# airrelay.net
KiCad netlist of a schematic drawn in EAGLE
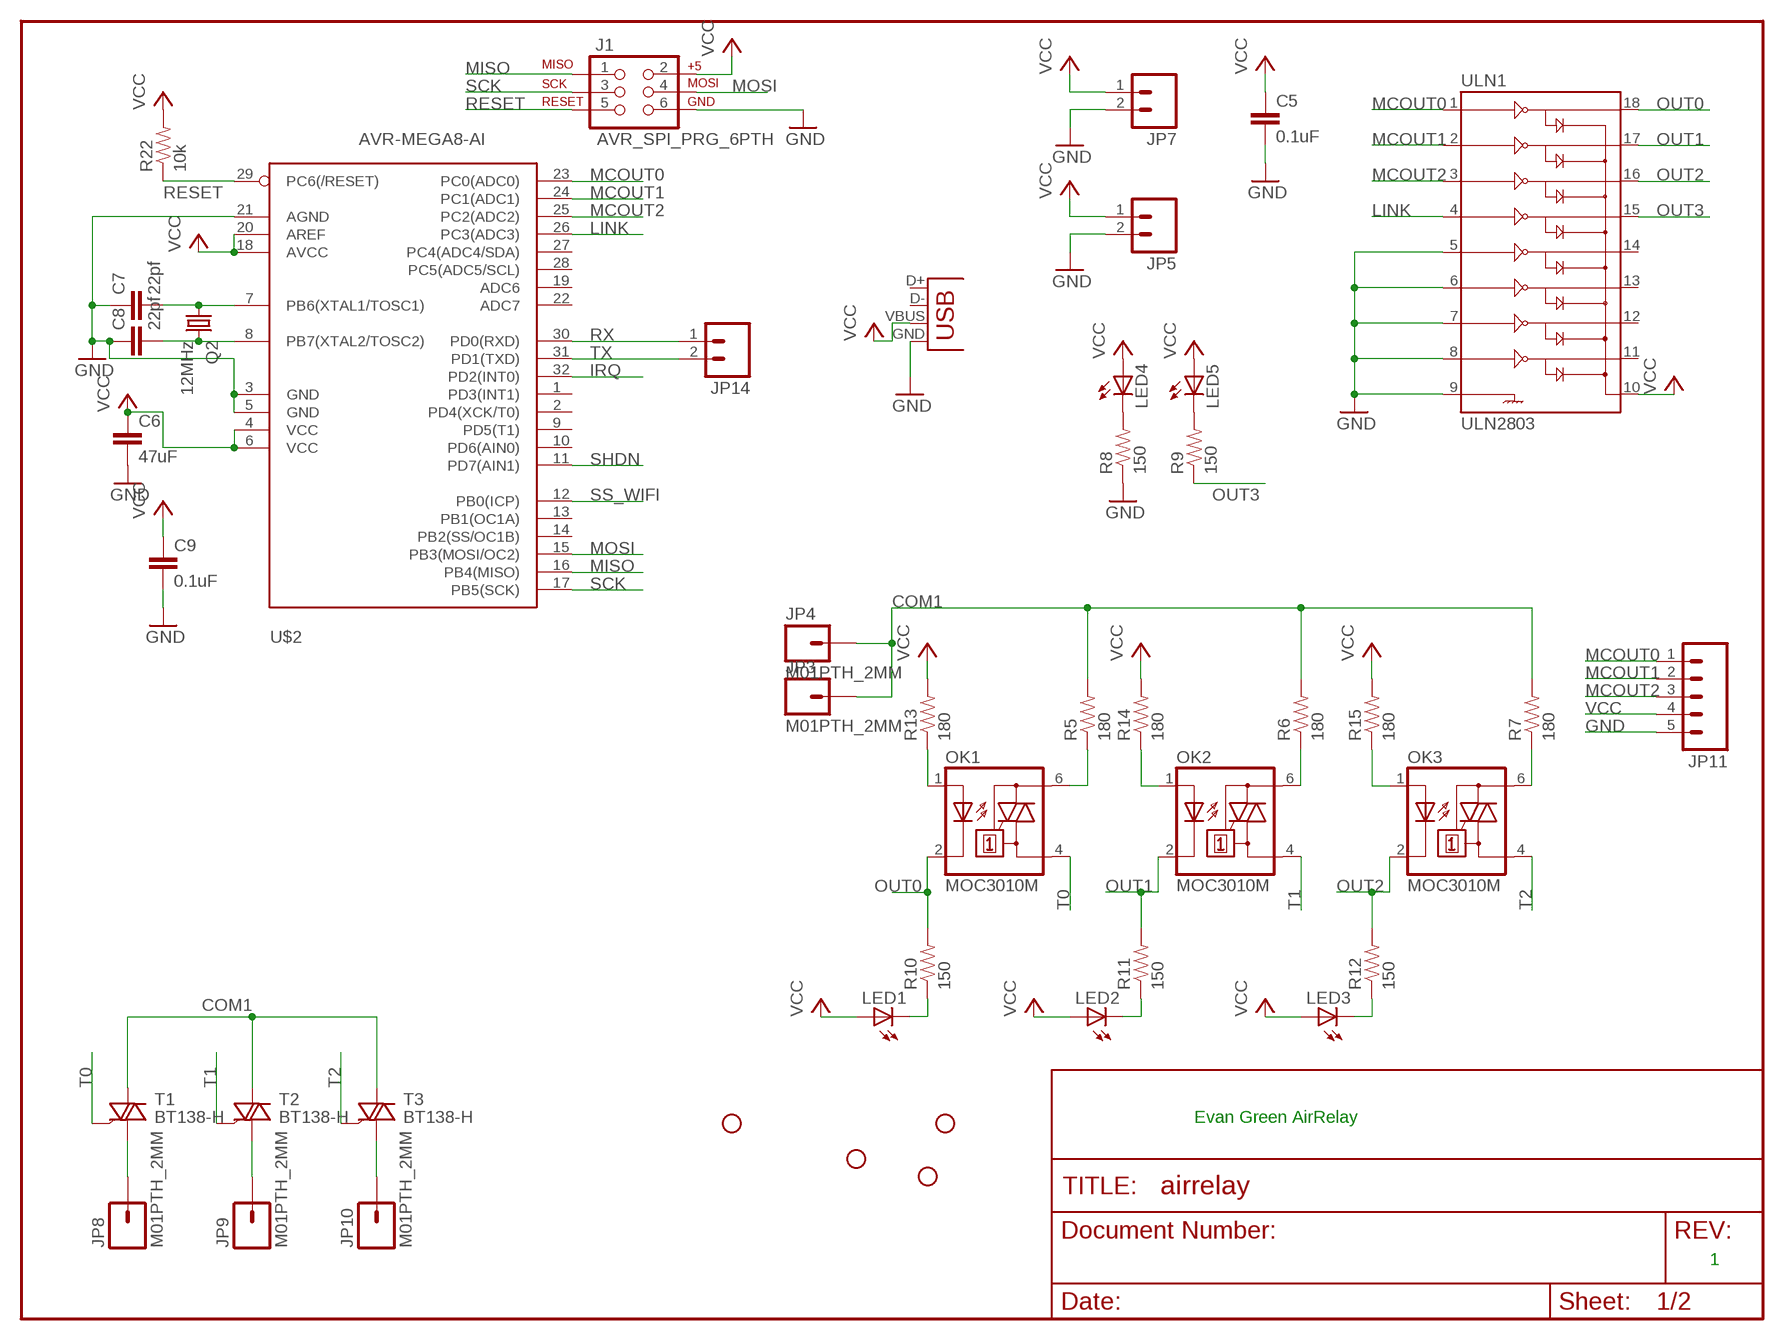
[diagram p0: schematic, sheet 1]
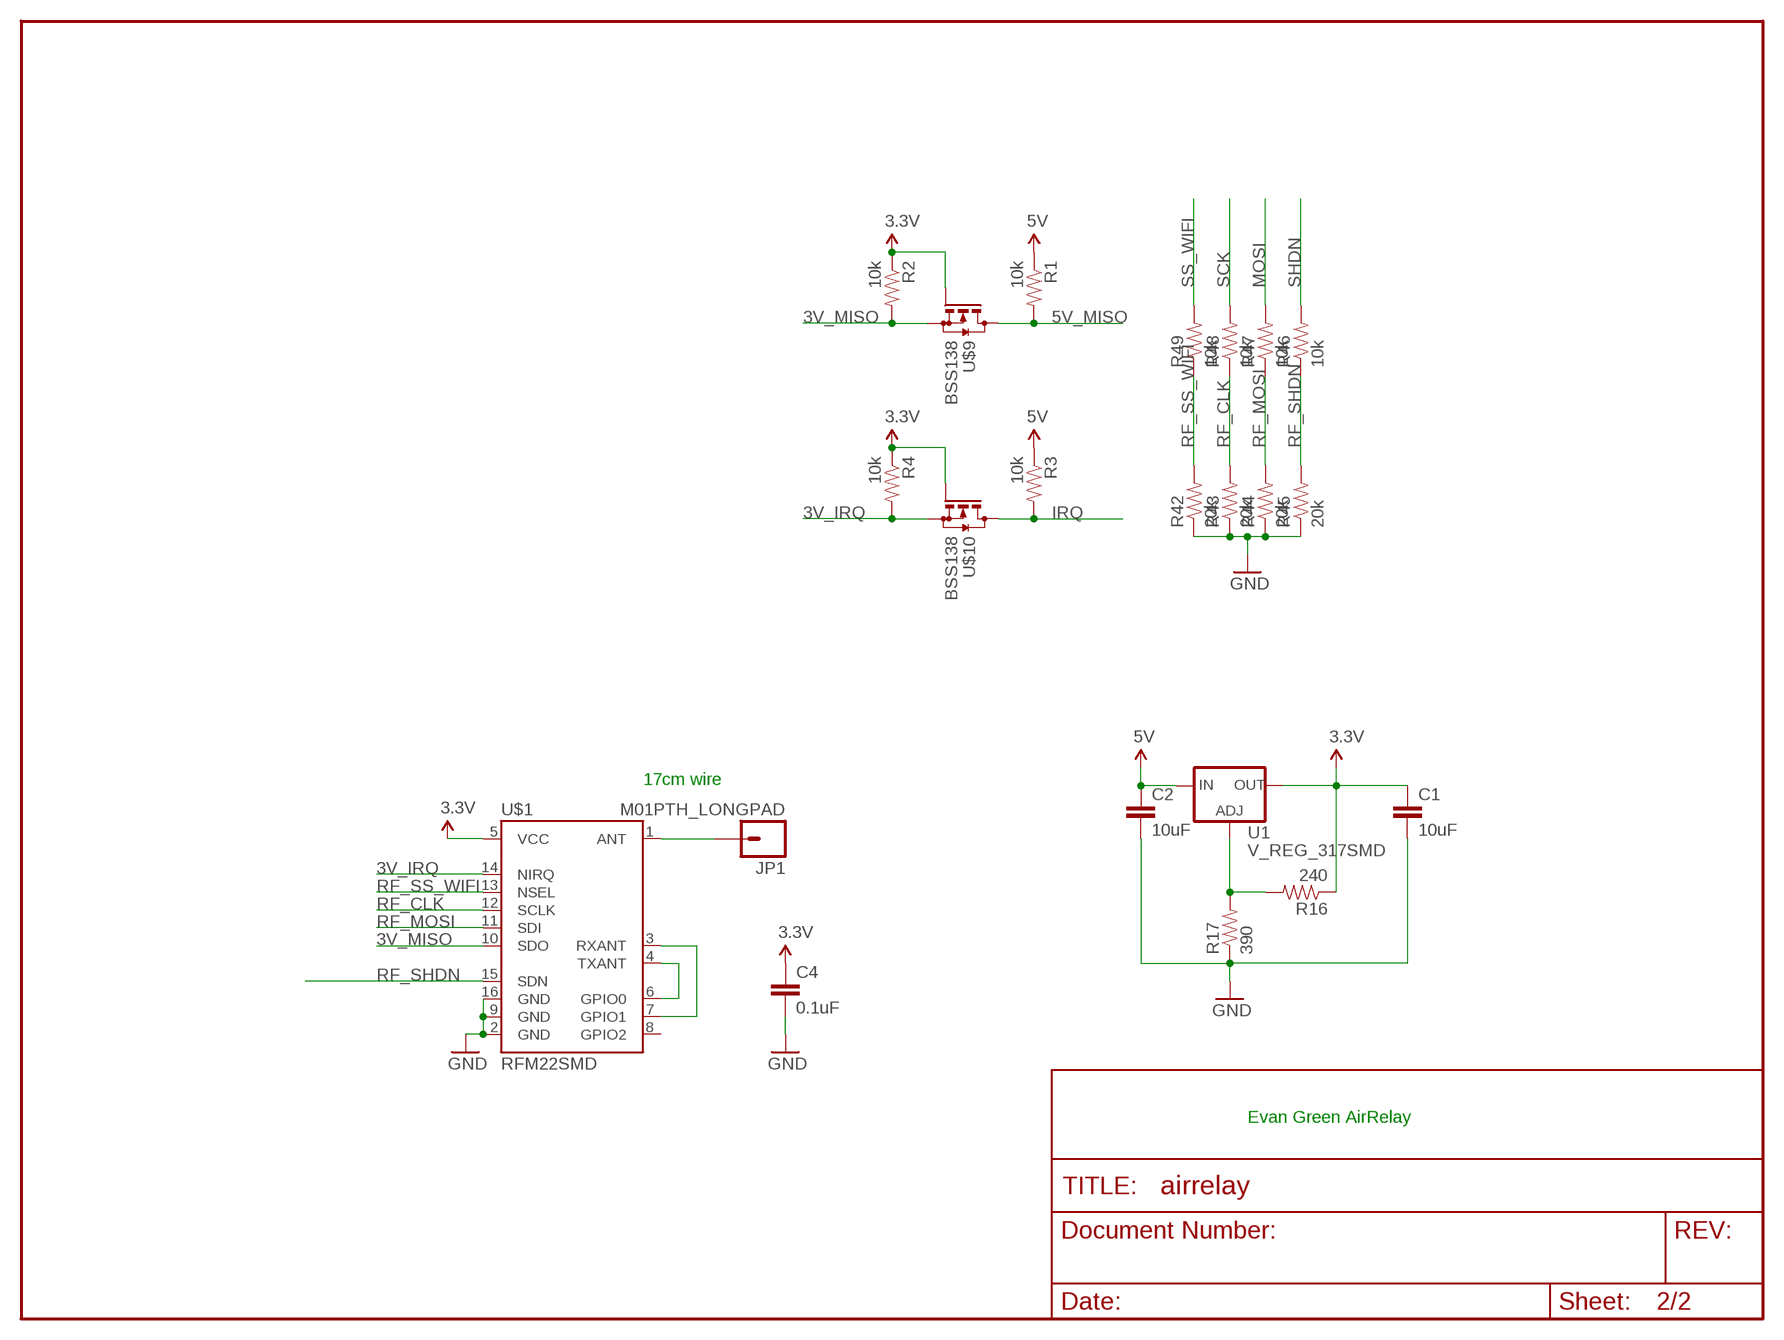
[diagram p1: schematic, sheet 2]

(export (version "E")
  (design (tool "Eeschema 10.0.6"))
  (components
    (comp (ref "C5")
      (value "0.1uF")
      (footprint "eagle-import:0402-CAP")
      (libsource (lib "eagle-import") (part "CAP0402-CAP"))
    )
    (comp (ref "C6")
      (value "47uF")
      (footprint "eagle-import:1210")
      (libsource (lib "eagle-import") (part "CAP1210"))
    )
    (comp (ref "C7")
      (value "22pf")
      (footprint "eagle-import:0402-CAP")
      (libsource (lib "eagle-import") (part "CAP0402-CAP"))
    )
    (comp (ref "C8")
      (value "22pf")
      (footprint "eagle-import:0402-CAP")
      (libsource (lib "eagle-import") (part "CAP0402-CAP"))
    )
    (comp (ref "C9")
      (value "0.1uF")
      (footprint "eagle-import:0402-CAP")
      (libsource (lib "eagle-import") (part "CAP0402-CAP"))
    )
    (comp (ref "J1")
      (value "AVR_SPI_PRG_6PTH")
      (footprint "eagle-import:2X3")
      (libsource (lib "eagle-import") (part "AVR_SPI_PRG_6PTH"))
    )
    (comp (ref "JP2")
      (value "STAND-OFF")
      (footprint "eagle-import:STAND-OFF")
      (libsource (lib "eagle-import") (part "STAND-OFF"))
    )
    (comp (ref "JP3")
      (value "M01PTH_2MM")
      (footprint "eagle-import:1X01_2MM")
      (libsource (lib "eagle-import") (part "M01PTH_2MM"))
    )
    (comp (ref "JP4")
      (value "M01PTH_2MM")
      (footprint "eagle-import:1X01_2MM")
      (libsource (lib "eagle-import") (part "M01PTH_2MM"))
    )
    (comp (ref "JP5")
      (value "M02PTH")
      (footprint "eagle-import:1X02")
      (libsource (lib "eagle-import") (part "M02PTH"))
    )
    (comp (ref "JP6")
      (value "STAND-OFF")
      (footprint "eagle-import:STAND-OFF")
      (libsource (lib "eagle-import") (part "STAND-OFF"))
    )
    (comp (ref "JP7")
      (value "M02PTH")
      (footprint "eagle-import:1X02")
      (libsource (lib "eagle-import") (part "M02PTH"))
    )
    (comp (ref "JP8")
      (value "M01PTH_2MM")
      (footprint "eagle-import:1X01_2MM")
      (libsource (lib "eagle-import") (part "M01PTH_2MM"))
    )
    (comp (ref "JP9")
      (value "M01PTH_2MM")
      (footprint "eagle-import:1X01_2MM")
      (libsource (lib "eagle-import") (part "M01PTH_2MM"))
    )
    (comp (ref "JP10")
      (value "M01PTH_2MM")
      (footprint "eagle-import:1X01_2MM")
      (libsource (lib "eagle-import") (part "M01PTH_2MM"))
    )
    (comp (ref "JP11")
      (value "M05PTH")
      (footprint "eagle-import:1X05")
      (libsource (lib "eagle-import") (part "M05PTH"))
    )
    (comp (ref "JP12")
      (value "STAND-OFF")
      (footprint "eagle-import:STAND-OFF")
      (libsource (lib "eagle-import") (part "STAND-OFF"))
    )
    (comp (ref "JP13")
      (value "STAND-OFF")
      (footprint "eagle-import:STAND-OFF")
      (libsource (lib "eagle-import") (part "STAND-OFF"))
    )
    (comp (ref "JP14")
      (value "M02PTH")
      (footprint "eagle-import:1X02")
      (libsource (lib "eagle-import") (part "M02PTH"))
    )
    (comp (ref "LED1")
      (value "LED5MM")
      (footprint "eagle-import:LED5MM")
      (libsource (lib "eagle-import") (part "LED5MM"))
    )
    (comp (ref "LED2")
      (value "LED5MM")
      (footprint "eagle-import:LED5MM")
      (libsource (lib "eagle-import") (part "LED5MM"))
    )
    (comp (ref "LED3")
      (value "LED5MM")
      (footprint "eagle-import:LED5MM")
      (libsource (lib "eagle-import") (part "LED5MM"))
    )
    (comp (ref "LED4")
      (value "LED3MM")
      (footprint "eagle-import:LED3MM")
      (libsource (lib "eagle-import") (part "LED3MM"))
    )
    (comp (ref "LED5")
      (value "LED3MM")
      (footprint "eagle-import:LED3MM")
      (libsource (lib "eagle-import") (part "LED3MM"))
    )
    (comp (ref "OK1")
      (value "MOC3010M")
      (footprint "eagle-import:DIL06")
      (fields (field (name "MF") "FAIRCHILD SEMICONDUCTOR") (field (name "MPN") "MOC3010-M"))
      (libsource (lib "eagle-import") (part "MOC30M10"))
    )
    (comp (ref "OK2")
      (value "MOC3010M")
      (footprint "eagle-import:DIL06")
      (fields (field (name "MF") "FAIRCHILD SEMICONDUCTOR") (field (name "MPN") "MOC3010-M"))
      (libsource (lib "eagle-import") (part "MOC30M10"))
    )
    (comp (ref "OK3")
      (value "MOC3010M")
      (footprint "eagle-import:DIL06")
      (fields (field (name "MF") "FAIRCHILD SEMICONDUCTOR") (field (name "MPN") "MOC3010-M"))
      (libsource (lib "eagle-import") (part "MOC30M10"))
    )
    (comp (ref "Q2")
      (value "12MHz")
      (footprint "eagle-import:TC38H")
      (libsource (lib "eagle-import") (part "CRYSTALTC38H"))
    )
    (comp (ref "R5")
      (value "180")
      (footprint "eagle-import:AXIAL-0.4")
      (libsource (lib "eagle-import") (part "RESISTORPTH-1/4W"))
    )
    (comp (ref "R6")
      (value "180")
      (footprint "eagle-import:AXIAL-0.4")
      (libsource (lib "eagle-import") (part "RESISTORPTH-1/4W"))
    )
    (comp (ref "R7")
      (value "180")
      (footprint "eagle-import:AXIAL-0.4")
      (libsource (lib "eagle-import") (part "RESISTORPTH-1/4W"))
    )
    (comp (ref "R8")
      (value "150")
      (footprint "eagle-import:0402-RES")
      (libsource (lib "eagle-import") (part "RESISTOR0402-RES"))
    )
    (comp (ref "R9")
      (value "150")
      (footprint "eagle-import:0402-RES")
      (libsource (lib "eagle-import") (part "RESISTOR0402-RES"))
    )
    (comp (ref "R10")
      (value "150")
      (footprint "eagle-import:0402-RES")
      (libsource (lib "eagle-import") (part "RESISTOR0402-RES"))
    )
    (comp (ref "R11")
      (value "150")
      (footprint "eagle-import:0402-RES")
      (libsource (lib "eagle-import") (part "RESISTOR0402-RES"))
    )
    (comp (ref "R12")
      (value "150")
      (footprint "eagle-import:0402-RES")
      (libsource (lib "eagle-import") (part "RESISTOR0402-RES"))
    )
    (comp (ref "R13")
      (value "180")
      (footprint "eagle-import:0402-RES")
      (libsource (lib "eagle-import") (part "RESISTOR0402-RES"))
    )
    (comp (ref "R14")
      (value "180")
      (footprint "eagle-import:0402-RES")
      (libsource (lib "eagle-import") (part "RESISTOR0402-RES"))
    )
    (comp (ref "R15")
      (value "180")
      (footprint "eagle-import:0402-RES")
      (libsource (lib "eagle-import") (part "RESISTOR0402-RES"))
    )
    (comp (ref "R22")
      (value "10k")
      (footprint "eagle-import:0402-RES")
      (libsource (lib "eagle-import") (part "RESISTOR0402-RES"))
    )
    (comp (ref "T1")
      (value "BT138-H")
      (footprint "eagle-import:TO220BH")
      (libsource (lib "eagle-import") (part "BT138-H"))
    )
    (comp (ref "T2")
      (value "BT138-H")
      (footprint "eagle-import:TO220BH")
      (libsource (lib "eagle-import") (part "BT138-H"))
    )
    (comp (ref "T3")
      (value "BT138-H")
      (footprint "eagle-import:TO220BH")
      (libsource (lib "eagle-import") (part "BT138-H"))
    )
    (comp (ref "U$2")
      (value "AVR-MEGA8-AI")
      (footprint "eagle-import:TQFP32-08")
      (libsource (lib "eagle-import") (part "AVR-MEGA8-AI"))
    )
    (comp (ref "ULN1")
      (value "ULN2803")
      (footprint "eagle-import:SO18L")
      (libsource (lib "eagle-import") (part "ULN2803SOICW"))
    )
    (comp (ref "X1")
      (value "USBSMD")
      (footprint "eagle-import:USB-MINIB")
      (libsource (lib "eagle-import") (part "USBSMD"))
    )
    (comp (ref "C1")
      (value "10uF")
      (footprint "eagle-import:0805")
      (libsource (lib "eagle-import") (part "CAP0805"))
    )
    (comp (ref "C2")
      (value "10uF")
      (footprint "eagle-import:0805")
      (libsource (lib "eagle-import") (part "CAP0805"))
    )
    (comp (ref "C4")
      (value "0.1uF")
      (footprint "eagle-import:0402-CAP")
      (libsource (lib "eagle-import") (part "CAP0402-CAP"))
    )
    (comp (ref "JP1")
      (value "M01PTH_LONGPAD")
      (footprint "eagle-import:1X01_LONGPAD")
      (libsource (lib "eagle-import") (part "M01PTH_LONGPAD"))
    )
    (comp (ref "R1")
      (value "10k")
      (footprint "eagle-import:0402-RES")
      (libsource (lib "eagle-import") (part "RESISTOR0402-RES"))
    )
    (comp (ref "R2")
      (value "10k")
      (footprint "eagle-import:0402-RES")
      (libsource (lib "eagle-import") (part "RESISTOR0402-RES"))
    )
    (comp (ref "R3")
      (value "10k")
      (footprint "eagle-import:0402-RES")
      (libsource (lib "eagle-import") (part "RESISTOR0402-RES"))
    )
    (comp (ref "R4")
      (value "10k")
      (footprint "eagle-import:0402-RES")
      (libsource (lib "eagle-import") (part "RESISTOR0402-RES"))
    )
    (comp (ref "R16")
      (value "240")
      (footprint "eagle-import:0402-RES")
      (libsource (lib "eagle-import") (part "RESISTOR0402-RES"))
    )
    (comp (ref "R17")
      (value "390")
      (footprint "eagle-import:0402-RES")
      (libsource (lib "eagle-import") (part "RESISTOR0402-RES"))
    )
    (comp (ref "R42")
      (value "20k")
      (footprint "eagle-import:0402-RES")
      (libsource (lib "eagle-import") (part "RESISTOR0402-RES"))
    )
    (comp (ref "R43")
      (value "20k")
      (footprint "eagle-import:0402-RES")
      (libsource (lib "eagle-import") (part "RESISTOR0402-RES"))
    )
    (comp (ref "R44")
      (value "20k")
      (footprint "eagle-import:0402-RES")
      (libsource (lib "eagle-import") (part "RESISTOR0402-RES"))
    )
    (comp (ref "R45")
      (value "20k")
      (footprint "eagle-import:0402-RES")
      (libsource (lib "eagle-import") (part "RESISTOR0402-RES"))
    )
    (comp (ref "R46")
      (value "10k")
      (footprint "eagle-import:0402-RES")
      (libsource (lib "eagle-import") (part "RESISTOR0402-RES"))
    )
    (comp (ref "R47")
      (value "10k")
      (footprint "eagle-import:0402-RES")
      (libsource (lib "eagle-import") (part "RESISTOR0402-RES"))
    )
    (comp (ref "R48")
      (value "10k")
      (footprint "eagle-import:0402-RES")
      (libsource (lib "eagle-import") (part "RESISTOR0402-RES"))
    )
    (comp (ref "R49")
      (value "10k")
      (footprint "eagle-import:0402-RES")
      (libsource (lib "eagle-import") (part "RESISTOR0402-RES"))
    )
    (comp (ref "U$1")
      (value "RFM22SMD")
      (footprint "eagle-import:RFM22-XXX-S2")
      (libsource (lib "eagle-import") (part "RFM22SMD"))
    )
    (comp (ref "U$9")
      (value "BSS138")
      (footprint "eagle-import:SOT-323")
      (libsource (lib "eagle-import") (part "BSS138"))
    )
    (comp (ref "U$10")
      (value "BSS138")
      (footprint "eagle-import:SOT-323")
      (libsource (lib "eagle-import") (part "BSS138"))
    )
    (comp (ref "U1")
      (value "V_REG_317SMD")
      (footprint "eagle-import:SOT223")
      (libsource (lib "eagle-import") (part "V_REG_317SMD"))
    )
  )
  (nets
    (net (code "1") (name "3.3V") (class "Default")
      (node (ref "C1") (pin "1") (pinfunction "1_1") (pintype "passive"))
      (node (ref "C4") (pin "1") (pinfunction "1_1") (pintype "passive"))
      (node (ref "R16") (pin "1") (pinfunction "1_1") (pintype "passive"))
      (node (ref "R2") (pin "1") (pinfunction "1_1") (pintype "passive"))
      (node (ref "R4") (pin "1") (pinfunction "1_1") (pintype "passive"))
      (node (ref "U$1") (pin "5") (pinfunction "VCC_5") (pintype "bidirectional"))
      (node (ref "U$10") (pin "1") (pinfunction "G_1") (pintype "passive"))
      (node (ref "U$9") (pin "1") (pinfunction "G_1") (pintype "passive"))
      (node (ref "U1") (pin "2") (pinfunction "OUT_2") (pintype "output"))
    )
    (net (code "2") (name "3V_IRQ") (class "Default")
      (node (ref "R4") (pin "2") (pinfunction "2_2") (pintype "passive"))
      (node (ref "U$1") (pin "14") (pinfunction "NIRQ_14") (pintype "output"))
      (node (ref "U$10") (pin "2") (pinfunction "S_2") (pintype "passive"))
    )
    (net (code "3") (name "3V_MISO") (class "Default")
      (node (ref "R2") (pin "2") (pinfunction "2_2") (pintype "passive"))
      (node (ref "U$1") (pin "10") (pinfunction "SDO_10") (pintype "output"))
      (node (ref "U$9") (pin "2") (pinfunction "S_2") (pintype "passive"))
    )
    (net (code "4") (name "5V") (class "Default")
      (node (ref "C2") (pin "1") (pinfunction "1_1") (pintype "passive"))
      (node (ref "R1") (pin "1") (pinfunction "1_1") (pintype "passive"))
      (node (ref "R3") (pin "1") (pinfunction "1_1") (pintype "passive"))
      (node (ref "U1") (pin "3") (pinfunction "IN_3") (pintype "input"))
    )
    (net (code "5") (name "5V_MISO") (class "Default")
      (node (ref "R1") (pin "2") (pinfunction "2_2") (pintype "passive"))
      (node (ref "U$9") (pin "3") (pinfunction "D_3") (pintype "passive"))
    )
    (net (code "6") (name "COM1") (class "Default")
      (node (ref "JP3") (pin "1") (pinfunction "1_1") (pintype "passive"))
      (node (ref "JP4") (pin "1") (pinfunction "1_1") (pintype "passive"))
      (node (ref "R5") (pin "P$2") (pinfunction "2_P$2") (pintype "passive"))
      (node (ref "R6") (pin "P$2") (pinfunction "2_P$2") (pintype "passive"))
      (node (ref "R7") (pin "P$2") (pinfunction "2_P$2") (pintype "passive"))
      (node (ref "T1") (pin "T2") (pinfunction "A2_T2") (pintype "passive"))
      (node (ref "T2") (pin "T2") (pinfunction "A2_T2") (pintype "passive"))
      (node (ref "T3") (pin "T2") (pinfunction "A2_T2") (pintype "passive"))
    )
    (net (code "7") (name "GND") (class "Default")
      (node (ref "C1") (pin "2") (pinfunction "2_2") (pintype "passive"))
      (node (ref "C2") (pin "2") (pinfunction "2_2") (pintype "passive"))
      (node (ref "C4") (pin "2") (pinfunction "2_2") (pintype "passive"))
      (node (ref "C5") (pin "2") (pinfunction "2_2") (pintype "passive"))
      (node (ref "C6") (pin "2") (pinfunction "2_2") (pintype "passive"))
      (node (ref "C7") (pin "1") (pinfunction "1_1") (pintype "passive"))
      (node (ref "C8") (pin "1") (pinfunction "1_1") (pintype "passive"))
      (node (ref "C9") (pin "2") (pinfunction "2_2") (pintype "passive"))
      (node (ref "J1") (pin "6") (pinfunction "6_6") (pintype "passive"))
      (node (ref "JP11") (pin "5") (pinfunction "5_5") (pintype "passive"))
      (node (ref "JP5") (pin "2") (pinfunction "2_2") (pintype "passive"))
      (node (ref "JP7") (pin "2") (pinfunction "2_2") (pintype "passive"))
      (node (ref "R17") (pin "1") (pinfunction "1_1") (pintype "passive"))
      (node (ref "R42") (pin "1") (pinfunction "1_1") (pintype "passive"))
      (node (ref "R43") (pin "1") (pinfunction "1_1") (pintype "passive"))
      (node (ref "R44") (pin "1") (pinfunction "1_1") (pintype "passive"))
      (node (ref "R45") (pin "1") (pinfunction "1_1") (pintype "passive"))
      (node (ref "R8") (pin "1") (pinfunction "1_1") (pintype "passive"))
      (node (ref "U$1") (pin "16") (pinfunction "GND_16") (pintype "power_in"))
      (node (ref "U$1") (pin "2") (pinfunction "GND_2") (pintype "power_in"))
      (node (ref "U$1") (pin "9") (pinfunction "GND_9") (pintype "power_in"))
      (node (ref "U$2") (pin "21") (pinfunction "AGND_21") (pintype "bidirectional"))
      (node (ref "U$2") (pin "3") (pinfunction "GND_3") (pintype "bidirectional"))
      (node (ref "U$2") (pin "5") (pinfunction "GND_5") (pintype "bidirectional"))
      (node (ref "ULN1") (pin "5") (pinfunction "5_5") (pintype "bidirectional"))
      (node (ref "ULN1") (pin "6") (pinfunction "6_6") (pintype "bidirectional"))
      (node (ref "ULN1") (pin "7") (pinfunction "7_7") (pintype "bidirectional"))
      (node (ref "ULN1") (pin "8") (pinfunction "8_8") (pintype "bidirectional"))
      (node (ref "ULN1") (pin "9") (pinfunction "9_9") (pintype "bidirectional"))
      (node (ref "X1") (pin "GND") (pinfunction "GND_GND") (pintype "bidirectional"))
    )
    (net (code "8") (name "IRQ") (class "Default")
      (node (ref "R3") (pin "2") (pinfunction "2_2") (pintype "passive"))
      (node (ref "U$10") (pin "3") (pinfunction "D_3") (pintype "passive"))
      (node (ref "U$2") (pin "32") (pinfunction "PD2(INT0)_32") (pintype "bidirectional"))
    )
    (net (code "9") (name "LINK") (class "Default")
      (node (ref "U$2") (pin "26") (pinfunction "PC3(ADC3)_26") (pintype "bidirectional"))
      (node (ref "ULN1") (pin "4") (pinfunction "4_4") (pintype "bidirectional"))
    )
    (net (code "10") (name "MCOUT0") (class "Default")
      (node (ref "JP11") (pin "1") (pinfunction "1_1") (pintype "passive"))
      (node (ref "U$2") (pin "23") (pinfunction "PC0(ADC0)_23") (pintype "bidirectional"))
      (node (ref "ULN1") (pin "1") (pinfunction "1_1") (pintype "bidirectional"))
    )
    (net (code "11") (name "MCOUT1") (class "Default")
      (node (ref "JP11") (pin "2") (pinfunction "2_2") (pintype "passive"))
      (node (ref "U$2") (pin "24") (pinfunction "PC1(ADC1)_24") (pintype "bidirectional"))
      (node (ref "ULN1") (pin "2") (pinfunction "2_2") (pintype "bidirectional"))
    )
    (net (code "12") (name "MCOUT2") (class "Default")
      (node (ref "JP11") (pin "3") (pinfunction "3_3") (pintype "passive"))
      (node (ref "U$2") (pin "25") (pinfunction "PC2(ADC2)_25") (pintype "bidirectional"))
      (node (ref "ULN1") (pin "3") (pinfunction "3_3") (pintype "bidirectional"))
    )
    (net (code "13") (name "MISO") (class "Default")
      (node (ref "J1") (pin "1") (pinfunction "1_1") (pintype "passive"))
      (node (ref "U$2") (pin "16") (pinfunction "PB4(MISO)_16") (pintype "bidirectional"))
    )
    (net (code "14") (name "MOSI") (class "Default")
      (node (ref "J1") (pin "4") (pinfunction "4_4") (pintype "passive"))
      (node (ref "R47") (pin "2") (pinfunction "2_2") (pintype "passive"))
      (node (ref "U$2") (pin "15") (pinfunction "PB3(MOSI/OC2)_15") (pintype "bidirectional"))
    )
    (net (code "15") (name "Net-(LED1-C)") (class "Default")
      (node (ref "LED1") (pin "K") (pinfunction "C_K") (pintype "passive"))
      (node (ref "R10") (pin "1") (pinfunction "1_1") (pintype "passive"))
    )
    (net (code "16") (name "Net-(LED2-C)") (class "Default")
      (node (ref "LED2") (pin "K") (pinfunction "C_K") (pintype "passive"))
      (node (ref "R11") (pin "1") (pinfunction "1_1") (pintype "passive"))
    )
    (net (code "17") (name "Net-(LED3-C)") (class "Default")
      (node (ref "LED3") (pin "K") (pinfunction "C_K") (pintype "passive"))
      (node (ref "R12") (pin "1") (pinfunction "1_1") (pintype "passive"))
    )
    (net (code "18") (name "Net-(LED4-C)") (class "Default")
      (node (ref "LED4") (pin "K") (pinfunction "C_K") (pintype "passive"))
      (node (ref "R8") (pin "2") (pinfunction "2_2") (pintype "passive"))
    )
    (net (code "19") (name "Net-(LED5-C)") (class "Default")
      (node (ref "LED5") (pin "K") (pinfunction "C_K") (pintype "passive"))
      (node (ref "R9") (pin "2") (pinfunction "2_2") (pintype "passive"))
    )
    (net (code "20") (name "Net-(OK1-A)") (class "Default")
      (node (ref "OK1") (pin "1") (pinfunction "A_1") (pintype "passive"))
      (node (ref "R13") (pin "1") (pinfunction "1_1") (pintype "passive"))
    )
    (net (code "21") (name "Net-(OK1-A2)") (class "Default")
      (node (ref "OK1") (pin "6") (pinfunction "A2_6") (pintype "passive"))
      (node (ref "R5") (pin "P$1") (pinfunction "1_P$1") (pintype "passive"))
    )
    (net (code "22") (name "Net-(OK2-A)") (class "Default")
      (node (ref "OK2") (pin "1") (pinfunction "A_1") (pintype "passive"))
      (node (ref "R14") (pin "1") (pinfunction "1_1") (pintype "passive"))
    )
    (net (code "23") (name "Net-(OK2-A2)") (class "Default")
      (node (ref "OK2") (pin "6") (pinfunction "A2_6") (pintype "passive"))
      (node (ref "R6") (pin "P$1") (pinfunction "1_P$1") (pintype "passive"))
    )
    (net (code "24") (name "Net-(OK3-A)") (class "Default")
      (node (ref "OK3") (pin "1") (pinfunction "A_1") (pintype "passive"))
      (node (ref "R15") (pin "1") (pinfunction "1_1") (pintype "passive"))
    )
    (net (code "25") (name "Net-(OK3-A2)") (class "Default")
      (node (ref "OK3") (pin "6") (pinfunction "A2_6") (pintype "passive"))
      (node (ref "R7") (pin "P$1") (pinfunction "1_P$1") (pintype "passive"))
    )
    (net (code "26") (name "Net-(T1-A1)") (class "Default")
      (node (ref "JP8") (pin "1") (pinfunction "1_1") (pintype "passive"))
      (node (ref "T1") (pin "T1") (pinfunction "A1_T1") (pintype "passive"))
    )
    (net (code "27") (name "Net-(T2-A1)") (class "Default")
      (node (ref "JP9") (pin "1") (pinfunction "1_1") (pintype "passive"))
      (node (ref "T2") (pin "T1") (pinfunction "A1_T1") (pintype "passive"))
    )
    (net (code "28") (name "Net-(T3-A1)") (class "Default")
      (node (ref "JP10") (pin "1") (pinfunction "1_1") (pintype "passive"))
      (node (ref "T3") (pin "T1") (pinfunction "A1_T1") (pintype "passive"))
    )
    (net (code "29") (name "Net-(U$1-ANT)") (class "Default")
      (node (ref "JP1") (pin "1") (pinfunction "1_1") (pintype "passive"))
      (node (ref "U$1") (pin "1") (pinfunction "ANT_1") (pintype "bidirectional"))
    )
    (net (code "30") (name "Net-(U$1-GPIO0)") (class "Default")
      (node (ref "U$1") (pin "4") (pinfunction "TXANT_4") (pintype "input"))
      (node (ref "U$1") (pin "6") (pinfunction "GPIO0_6") (pintype "bidirectional"))
    )
    (net (code "31") (name "Net-(U$1-GPIO1)") (class "Default")
      (node (ref "U$1") (pin "3") (pinfunction "RXANT_3") (pintype "input"))
      (node (ref "U$1") (pin "7") (pinfunction "GPIO1_7") (pintype "bidirectional"))
    )
    (net (code "32") (name "Net-(U$2-PB6(XTAL1{slash}TOSC1))") (class "Default")
      (node (ref "C7") (pin "2") (pinfunction "2_2") (pintype "passive"))
      (node (ref "Q2") (pin "1") (pinfunction "1_1") (pintype "passive"))
      (node (ref "U$2") (pin "7") (pinfunction "PB6(XTAL1/TOSC1)_7") (pintype "bidirectional"))
    )
    (net (code "33") (name "Net-(U$2-PB7(XTAL2{slash}TOSC2))") (class "Default")
      (node (ref "C8") (pin "2") (pinfunction "2_2") (pintype "passive"))
      (node (ref "Q2") (pin "2") (pinfunction "2_2") (pintype "passive"))
      (node (ref "U$2") (pin "8") (pinfunction "PB7(XTAL2/TOSC2)_8") (pintype "bidirectional"))
    )
    (net (code "34") (name "Net-(U1-ADJ)") (class "Default")
      (node (ref "R16") (pin "2") (pinfunction "2_2") (pintype "passive"))
      (node (ref "R17") (pin "2") (pinfunction "2_2") (pintype "passive"))
      (node (ref "U1") (pin "1") (pinfunction "ADJ_1") (pintype "input"))
    )
    (net (code "35") (name "OUT0") (class "Default")
      (node (ref "OK1") (pin "2") (pinfunction "C_2") (pintype "passive"))
      (node (ref "R10") (pin "2") (pinfunction "2_2") (pintype "passive"))
      (node (ref "ULN1") (pin "18") (pinfunction "18_18") (pintype "bidirectional"))
    )
    (net (code "36") (name "OUT1") (class "Default")
      (node (ref "OK2") (pin "2") (pinfunction "C_2") (pintype "passive"))
      (node (ref "R11") (pin "2") (pinfunction "2_2") (pintype "passive"))
      (node (ref "ULN1") (pin "17") (pinfunction "17_17") (pintype "bidirectional"))
    )
    (net (code "37") (name "OUT2") (class "Default")
      (node (ref "OK3") (pin "2") (pinfunction "C_2") (pintype "passive"))
      (node (ref "R12") (pin "2") (pinfunction "2_2") (pintype "passive"))
      (node (ref "ULN1") (pin "16") (pinfunction "16_16") (pintype "bidirectional"))
    )
    (net (code "38") (name "OUT3") (class "Default")
      (node (ref "R9") (pin "1") (pinfunction "1_1") (pintype "passive"))
      (node (ref "ULN1") (pin "15") (pinfunction "15_15") (pintype "bidirectional"))
    )
    (net (code "39") (name "RESET") (class "Default")
      (node (ref "J1") (pin "5") (pinfunction "5_5") (pintype "passive"))
      (node (ref "R22") (pin "1") (pinfunction "1_1") (pintype "passive"))
      (node (ref "U$2") (pin "29") (pinfunction "PC6(/RESET)_29") (pintype "bidirectional"))
    )
    (net (code "40") (name "RF_CLK") (class "Default")
      (node (ref "R43") (pin "2") (pinfunction "2_2") (pintype "passive"))
      (node (ref "R48") (pin "1") (pinfunction "1_1") (pintype "passive"))
      (node (ref "U$1") (pin "12") (pinfunction "SCLK_12") (pintype "input"))
    )
    (net (code "41") (name "RF_MOSI") (class "Default")
      (node (ref "R44") (pin "2") (pinfunction "2_2") (pintype "passive"))
      (node (ref "R47") (pin "1") (pinfunction "1_1") (pintype "passive"))
      (node (ref "U$1") (pin "11") (pinfunction "SDI_11") (pintype "input"))
    )
    (net (code "42") (name "RF_SHDN") (class "Default")
      (node (ref "R45") (pin "2") (pinfunction "2_2") (pintype "passive"))
      (node (ref "R46") (pin "1") (pinfunction "1_1") (pintype "passive"))
      (node (ref "U$1") (pin "15") (pinfunction "SDN_15") (pintype "input"))
    )
    (net (code "43") (name "RF_SS_WIFI") (class "Default")
      (node (ref "R42") (pin "2") (pinfunction "2_2") (pintype "passive"))
      (node (ref "R49") (pin "1") (pinfunction "1_1") (pintype "passive"))
      (node (ref "U$1") (pin "13") (pinfunction "NSEL_13") (pintype "input"))
    )
    (net (code "44") (name "RX") (class "Default")
      (node (ref "JP14") (pin "1") (pinfunction "1_1") (pintype "passive"))
      (node (ref "U$2") (pin "30") (pinfunction "PD0(RXD)_30") (pintype "bidirectional"))
    )
    (net (code "45") (name "SCK") (class "Default")
      (node (ref "J1") (pin "3") (pinfunction "3_3") (pintype "passive"))
      (node (ref "R48") (pin "2") (pinfunction "2_2") (pintype "passive"))
      (node (ref "U$2") (pin "17") (pinfunction "PB5(SCK)_17") (pintype "bidirectional"))
    )
    (net (code "46") (name "SHDN") (class "Default")
      (node (ref "R46") (pin "2") (pinfunction "2_2") (pintype "passive"))
      (node (ref "U$2") (pin "11") (pinfunction "PD7(AIN1)_11") (pintype "bidirectional"))
    )
    (net (code "47") (name "SS_WIFI") (class "Default")
      (node (ref "R49") (pin "2") (pinfunction "2_2") (pintype "passive"))
      (node (ref "U$2") (pin "12") (pinfunction "PB0(ICP)_12") (pintype "bidirectional"))
    )
    (net (code "48") (name "T0") (class "Default")
      (node (ref "OK1") (pin "4") (pinfunction "A1_4") (pintype "passive"))
      (node (ref "T1") (pin "G") (pinfunction "G_G") (pintype "passive"))
    )
    (net (code "49") (name "T1") (class "Default")
      (node (ref "OK2") (pin "4") (pinfunction "A1_4") (pintype "passive"))
      (node (ref "T2") (pin "G") (pinfunction "G_G") (pintype "passive"))
    )
    (net (code "50") (name "T2") (class "Default")
      (node (ref "OK3") (pin "4") (pinfunction "A1_4") (pintype "passive"))
      (node (ref "T3") (pin "G") (pinfunction "G_G") (pintype "passive"))
    )
    (net (code "51") (name "TX") (class "Default")
      (node (ref "JP14") (pin "2") (pinfunction "2_2") (pintype "passive"))
      (node (ref "U$2") (pin "31") (pinfunction "PD1(TXD)_31") (pintype "bidirectional"))
    )
    (net (code "52") (name "VCC") (class "Default")
      (node (ref "C5") (pin "1") (pinfunction "1_1") (pintype "passive"))
      (node (ref "C6") (pin "1") (pinfunction "1_1") (pintype "passive"))
      (node (ref "C9") (pin "1") (pinfunction "1_1") (pintype "passive"))
      (node (ref "J1") (pin "2") (pinfunction "2_2") (pintype "passive"))
      (node (ref "JP11") (pin "4") (pinfunction "4_4") (pintype "passive"))
      (node (ref "JP5") (pin "1") (pinfunction "1_1") (pintype "passive"))
      (node (ref "JP7") (pin "1") (pinfunction "1_1") (pintype "passive"))
      (node (ref "LED1") (pin "A") (pinfunction "A_A") (pintype "passive"))
      (node (ref "LED2") (pin "A") (pinfunction "A_A") (pintype "passive"))
      (node (ref "LED3") (pin "A") (pinfunction "A_A") (pintype "passive"))
      (node (ref "LED4") (pin "A") (pinfunction "A_A") (pintype "passive"))
      (node (ref "LED5") (pin "A") (pinfunction "A_A") (pintype "passive"))
      (node (ref "R13") (pin "2") (pinfunction "2_2") (pintype "passive"))
      (node (ref "R14") (pin "2") (pinfunction "2_2") (pintype "passive"))
      (node (ref "R15") (pin "2") (pinfunction "2_2") (pintype "passive"))
      (node (ref "R22") (pin "2") (pinfunction "2_2") (pintype "passive"))
      (node (ref "U$2") (pin "18") (pinfunction "AVCC_18") (pintype "bidirectional"))
      (node (ref "U$2") (pin "20") (pinfunction "AREF_20") (pintype "bidirectional"))
      (node (ref "U$2") (pin "4") (pinfunction "VCC_4") (pintype "bidirectional"))
      (node (ref "U$2") (pin "6") (pinfunction "VCC_6") (pintype "bidirectional"))
      (node (ref "ULN1") (pin "10") (pinfunction "10_10") (pintype "bidirectional"))
      (node (ref "X1") (pin "VBUS") (pinfunction "VBUS_VBUS") (pintype "bidirectional"))
    )
    (net (code "53") (name "unconnected-(U$1-GPIO2-Pad8)") (class "Default")
      (node (ref "U$1") (pin "8") (pinfunction "GPIO2_8") (pintype "bidirectional"))
    )
    (net (code "54") (name "unconnected-(U$2-ADC6-Pad19)") (class "Default")
      (node (ref "U$2") (pin "19") (pinfunction "ADC6_19") (pintype "bidirectional"))
    )
    (net (code "55") (name "unconnected-(U$2-ADC7-Pad22)") (class "Default")
      (node (ref "U$2") (pin "22") (pinfunction "ADC7_22") (pintype "bidirectional"))
    )
    (net (code "56") (name "unconnected-(U$2-PB1(OC1A)-Pad13)") (class "Default")
      (node (ref "U$2") (pin "13") (pinfunction "PB1(OC1A)_13") (pintype "bidirectional"))
    )
    (net (code "57") (name "unconnected-(U$2-PB2(SS{slash}OC1B)-Pad14)") (class "Default")
      (node (ref "U$2") (pin "14") (pinfunction "PB2(SS/OC1B)_14") (pintype "bidirectional"))
    )
    (net (code "58") (name "unconnected-(U$2-PC4(ADC4{slash}SDA)-Pad27)") (class "Default")
      (node (ref "U$2") (pin "27") (pinfunction "PC4(ADC4/SDA)_27") (pintype "bidirectional"))
    )
    (net (code "59") (name "unconnected-(U$2-PC5(ADC5{slash}SCL)-Pad28)") (class "Default")
      (node (ref "U$2") (pin "28") (pinfunction "PC5(ADC5/SCL)_28") (pintype "bidirectional"))
    )
    (net (code "60") (name "unconnected-(U$2-PD3(INT1)-Pad1)") (class "Default")
      (node (ref "U$2") (pin "1") (pinfunction "PD3(INT1)_1") (pintype "bidirectional"))
    )
    (net (code "61") (name "unconnected-(U$2-PD4(XCK{slash}T0)-Pad2)") (class "Default")
      (node (ref "U$2") (pin "2") (pinfunction "PD4(XCK/T0)_2") (pintype "bidirectional"))
    )
    (net (code "62") (name "unconnected-(U$2-PD5(T1)-Pad9)") (class "Default")
      (node (ref "U$2") (pin "9") (pinfunction "PD5(T1)_9") (pintype "bidirectional"))
    )
    (net (code "63") (name "unconnected-(U$2-PD6(AIN0)-Pad10)") (class "Default")
      (node (ref "U$2") (pin "10") (pinfunction "PD6(AIN0)_10") (pintype "bidirectional"))
    )
    (net (code "64") (name "unconnected-(ULN1-Pad11)") (class "Default")
      (node (ref "ULN1") (pin "11") (pinfunction "11_11") (pintype "bidirectional"))
    )
    (net (code "65") (name "unconnected-(ULN1-Pad12)") (class "Default")
      (node (ref "ULN1") (pin "12") (pinfunction "12_12") (pintype "bidirectional"))
    )
    (net (code "66") (name "unconnected-(ULN1-Pad13)") (class "Default")
      (node (ref "ULN1") (pin "13") (pinfunction "13_13") (pintype "bidirectional"))
    )
    (net (code "67") (name "unconnected-(ULN1-Pad14)") (class "Default")
      (node (ref "ULN1") (pin "14") (pinfunction "14_14") (pintype "bidirectional"))
    )
    (net (code "68") (name "unconnected-(X1-PadD+)") (class "Default")
      (node (ref "X1") (pin "D+") (pinfunction "D+_D+") (pintype "bidirectional"))
    )
    (net (code "69") (name "unconnected-(X1-PadD-)") (class "Default")
      (node (ref "X1") (pin "D-") (pinfunction "D-_D-") (pintype "bidirectional"))
    )
  )
)
